# breakout_pmg001.net
KiCad netlist of a schematic drawn in EAGLE
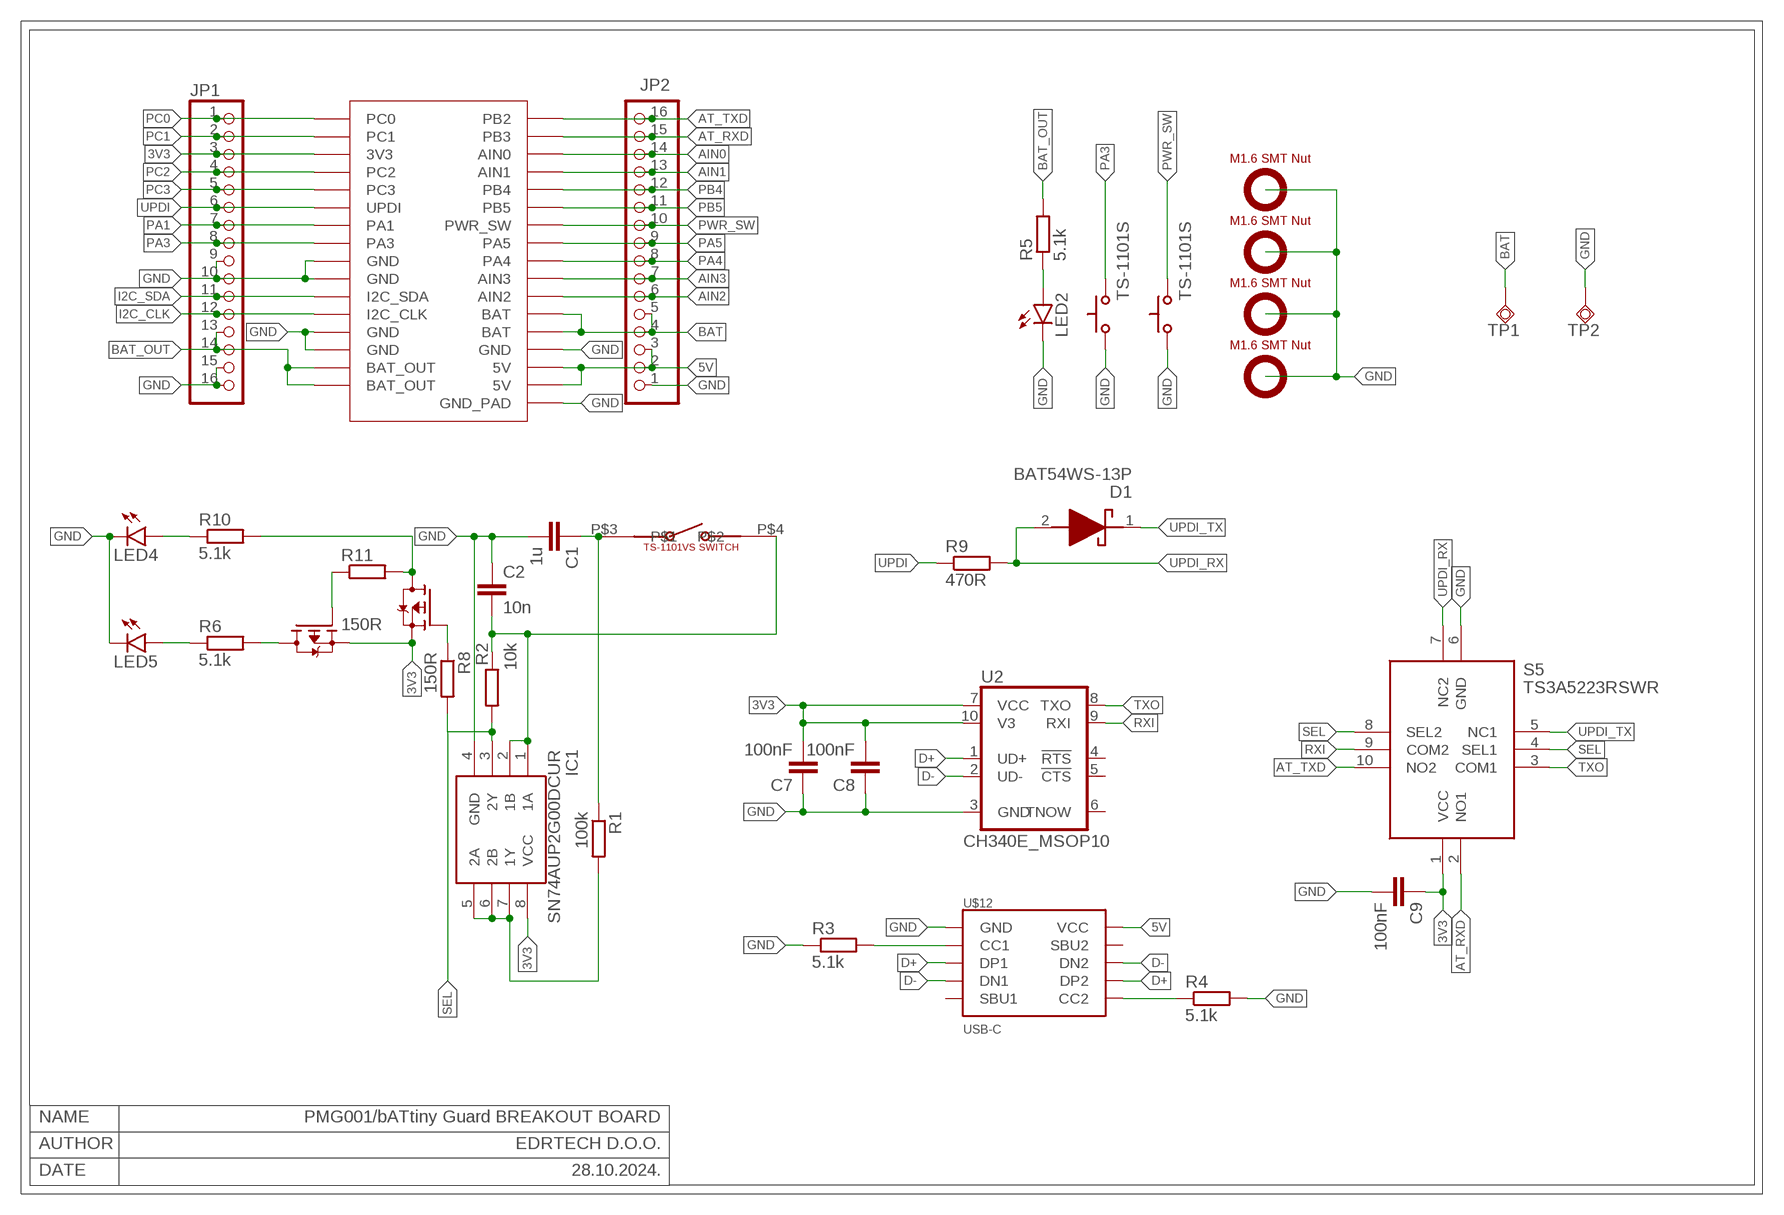
[diagram p0: schematic, sheet 1]

(export (version "E")
  (design (tool "Eeschema 10.0.6"))
  (components
    (comp (ref "C1")
      (value "1u")
      (footprint "eagle-import:C0402")
      (libsource (lib "eagle-import") (part "C-EUC0402"))
    )
    (comp (ref "C2")
      (value "10n")
      (footprint "eagle-import:C0402")
      (libsource (lib "eagle-import") (part "C-EUC0402"))
    )
    (comp (ref "C7")
      (value "100nF")
      (footprint "eagle-import:C0402")
      (libsource (lib "eagle-import") (part "C-EUC0402"))
    )
    (comp (ref "C8")
      (value "100nF")
      (footprint "eagle-import:C0402")
      (libsource (lib "eagle-import") (part "C-EUC0402"))
    )
    (comp (ref "C9")
      (value "100nF")
      (footprint "eagle-import:C0402")
      (libsource (lib "eagle-import") (part "C-EUC0402"))
    )
    (comp (ref "D1")
      (value "BAT54WS-13P")
      (footprint "eagle-import:SOD2512X115N")
      (libsource (lib "eagle-import") (part "BAT54WS-13P"))
    )
    (comp (ref "IC1")
      (value "SN74AUP2G00DCUR")
      (footprint "eagle-import:SOP50P310X90-8N")
      (fields (field (name "MOUSER_PART_NUMBER") "595-SN74AUP2G00DCUR"))
      (libsource (lib "eagle-import") (part "SN74AUP2G00DCUR"))
    )
    (comp (ref "JP1")
      (value "PINHD-1X16")
      (footprint "eagle-import:1X16")
      (libsource (lib "eagle-import") (part "PINHD-1X16"))
    )
    (comp (ref "JP2")
      (value "PINHD-1X16")
      (footprint "eagle-import:1X16")
      (libsource (lib "eagle-import") (part "PINHD-1X16"))
    )
    (comp (ref "LED2")
      (value "LEDCHIP-LED0603")
      (footprint "eagle-import:CHIP-LED0603")
      (libsource (lib "eagle-import") (part "LEDCHIP-LED0603"))
    )
    (comp (ref "LED4")
      (value "LEDCHIP-LED0603")
      (footprint "eagle-import:CHIP-LED0603")
      (libsource (lib "eagle-import") (part "LEDCHIP-LED0603"))
    )
    (comp (ref "LED5")
      (value "LEDCHIP-LED0603")
      (footprint "eagle-import:CHIP-LED0603")
      (libsource (lib "eagle-import") (part "LEDCHIP-LED0603"))
    )
    (comp (ref "Q1")
      (value "NTK3139PT1G")
      (footprint "eagle-import:SOTFL40P120X55-3N")
      (fields (field (name "MOUSER_PART_NUMBER") "863-NTK3139PT1G"))
      (libsource (lib "eagle-import") (part "NTK3139PT1G"))
    )
    (comp (ref "Q2")
      (value "NTK3139PT1G")
      (footprint "eagle-import:SOTFL40P120X55-3N")
      (fields (field (name "MOUSER_PART_NUMBER") "863-NTK3139PT1G"))
      (libsource (lib "eagle-import") (part "NTK3139PT1G"))
    )
    (comp (ref "R1")
      (value "100k")
      (footprint "eagle-import:R0402")
      (libsource (lib "eagle-import") (part "R-EU_R0402"))
    )
    (comp (ref "R2")
      (value "10k")
      (footprint "eagle-import:R0402")
      (libsource (lib "eagle-import") (part "R-EU_R0402"))
    )
    (comp (ref "R3")
      (value "5.1k")
      (footprint "eagle-import:R0402")
      (libsource (lib "eagle-import") (part "R-EU_R0402"))
    )
    (comp (ref "R4")
      (value "5.1k")
      (footprint "eagle-import:R0402")
      (libsource (lib "eagle-import") (part "R-EU_R0402"))
    )
    (comp (ref "R5")
      (value "5.1k")
      (footprint "eagle-import:R0402")
      (libsource (lib "eagle-import") (part "R-EU_R0402"))
    )
    (comp (ref "R6")
      (value "5.1k")
      (footprint "eagle-import:R0402")
      (libsource (lib "eagle-import") (part "R-EU_R0402"))
    )
    (comp (ref "R8")
      (value "150R")
      (footprint "eagle-import:R0402")
      (libsource (lib "eagle-import") (part "R-EU_R0402"))
    )
    (comp (ref "R9")
      (value "470R")
      (footprint "eagle-import:R0402")
      (libsource (lib "eagle-import") (part "R-EU_R0402"))
    )
    (comp (ref "R10")
      (value "5.1k")
      (footprint "eagle-import:R0402")
      (libsource (lib "eagle-import") (part "R-EU_R0402"))
    )
    (comp (ref "R11")
      (value "150R")
      (footprint "eagle-import:R0402")
      (libsource (lib "eagle-import") (part "R-EU_R0402"))
    )
    (comp (ref "S5")
      (value "TS3A5223RSWR")
      (footprint "eagle-import:RSW(RPUQFNN10)")
      (fields (field (name "MOUSER_PART_NUMBER") "595-TS3A5223RSWR"))
      (libsource (lib "eagle-import") (part "TS3A5223RSWR"))
    )
    (comp (ref "TP1")
      (value "TPSQTP19SQ")
      (footprint "eagle-import:TP19SQ")
      (libsource (lib "eagle-import") (part "TPSQTP19SQ"))
    )
    (comp (ref "TP2")
      (value "TPSQTP19SQ")
      (footprint "eagle-import:TP19SQ")
      (libsource (lib "eagle-import") (part "TPSQTP19SQ"))
    )
    (comp (ref "U$1")
      (value "TS-1101S")
      (footprint "eagle-import:TS-1101S")
      (libsource (lib "eagle-import") (part "TS-1101S"))
    )
    (comp (ref "U$2")
      (value "TS-1101VS-C-A-A")
      (footprint "eagle-import:TS-1101VS-C-A-A")
      (libsource (lib "eagle-import") (part "TS-1101VS-C-A-A"))
    )
    (comp (ref "U$4")
      (value "TS-1101S")
      (footprint "eagle-import:TS-1101S")
      (libsource (lib "eagle-import") (part "TS-1101S"))
    )
    (comp (ref "U$7")
      (value "PMG001")
      (footprint "eagle-import:PMG001")
      (libsource (lib "eagle-import") (part "PMG001"))
    )
    (comp (ref "U$8")
      (value "SMTSO16")
      (footprint "eagle-import:SMTSO16")
      (libsource (lib "eagle-import") (part "SMTSO16"))
    )
    (comp (ref "U$9")
      (value "SMTSO16")
      (footprint "eagle-import:SMTSO16")
      (libsource (lib "eagle-import") (part "SMTSO16"))
    )
    (comp (ref "U$10")
      (value "SMTSO16")
      (footprint "eagle-import:SMTSO16")
      (libsource (lib "eagle-import") (part "SMTSO16"))
    )
    (comp (ref "U$11")
      (value "SMTSO16")
      (footprint "eagle-import:SMTSO16")
      (libsource (lib "eagle-import") (part "SMTSO16"))
    )
    (comp (ref "U$12")
      (value "USB-C")
      (footprint "eagle-import:USB-C")
      (libsource (lib "eagle-import") (part "USB-C"))
    )
    (comp (ref "U2")
      (value "CH340E_MSOP10")
      (footprint "eagle-import:MSOP10")
      (fields (field (name "MF") "WCH") (field (name "MP") "CH340E"))
      (libsource (lib "eagle-import") (part "CH340E_MSOP10"))
    )
  )
  (nets
    (net (code "1") (name "3V3") (class "Default")
      (node (ref "C7") (pin "2") (pinfunction "2_2") (pintype "passive"))
      (node (ref "C8") (pin "2") (pinfunction "2_2") (pintype "passive"))
      (node (ref "C9") (pin "1") (pinfunction "1_1") (pintype "passive"))
      (node (ref "IC1") (pin "8") (pinfunction "VCC_8") (pintype "bidirectional"))
      (node (ref "JP1") (pin "3") (pinfunction "3_3") (pintype "passive"))
      (node (ref "Q1") (pin "2") (pinfunction "S_2") (pintype "passive"))
      (node (ref "Q2") (pin "2") (pinfunction "S_2") (pintype "passive"))
      (node (ref "S5") (pin "1") (pinfunction "VCC_1") (pintype "power_in"))
      (node (ref "U$7") (pin "P$3") (pinfunction "3V3_P$3") (pintype "bidirectional"))
      (node (ref "U2") (pin "10") (pinfunction "V3_10") (pintype "bidirectional"))
      (node (ref "U2") (pin "7") (pinfunction "VCC_7") (pintype "bidirectional"))
    )
    (net (code "2") (name "5V") (class "Default")
      (node (ref "JP2") (pin "2") (pinfunction "2_2") (pintype "passive"))
      (node (ref "JP2") (pin "3") (pinfunction "3_3") (pintype "passive"))
      (node (ref "U$12") (pin "VCC@1") (pinfunction "VCC_VCC@1") (pintype "bidirectional"))
      (node (ref "U$12") (pin "VCC@2") (pinfunction "VCC_VCC@2") (pintype "bidirectional"))
      (node (ref "U$7") (pin "P$17") (pinfunction "5V_P$17") (pintype "bidirectional"))
      (node (ref "U$7") (pin "P$18") (pinfunction "5V_P$18") (pintype "bidirectional"))
    )
    (net (code "3") (name "AIN0") (class "Default")
      (node (ref "JP2") (pin "14") (pinfunction "14_14") (pintype "passive"))
      (node (ref "U$7") (pin "P$30") (pinfunction "AIN0_P$30") (pintype "bidirectional"))
    )
    (net (code "4") (name "AIN1") (class "Default")
      (node (ref "JP2") (pin "13") (pinfunction "13_13") (pintype "passive"))
      (node (ref "U$7") (pin "P$29") (pinfunction "AIN1_P$29") (pintype "bidirectional"))
    )
    (net (code "5") (name "AIN2") (class "Default")
      (node (ref "JP2") (pin "6") (pinfunction "6_6") (pintype "passive"))
      (node (ref "U$7") (pin "P$22") (pinfunction "AIN2_P$22") (pintype "bidirectional"))
    )
    (net (code "6") (name "AIN3") (class "Default")
      (node (ref "JP2") (pin "7") (pinfunction "7_7") (pintype "passive"))
      (node (ref "U$7") (pin "P$23") (pinfunction "AIN3_P$23") (pintype "bidirectional"))
    )
    (net (code "7") (name "AT_RXD") (class "Default")
      (node (ref "JP2") (pin "15") (pinfunction "15_15") (pintype "passive"))
      (node (ref "S5") (pin "2") (pinfunction "NO1_2") (pintype "bidirectional"))
      (node (ref "U$7") (pin "P$31") (pinfunction "PB3_P$31") (pintype "bidirectional"))
    )
    (net (code "8") (name "AT_TXD") (class "Default")
      (node (ref "JP2") (pin "16") (pinfunction "16_16") (pintype "passive"))
      (node (ref "S5") (pin "10") (pinfunction "NO2_10") (pintype "bidirectional"))
      (node (ref "U$7") (pin "P$32") (pinfunction "PB2_P$32") (pintype "bidirectional"))
    )
    (net (code "9") (name "BAT") (class "Default")
      (node (ref "JP2") (pin "4") (pinfunction "4_4") (pintype "passive"))
      (node (ref "JP2") (pin "5") (pinfunction "5_5") (pintype "passive"))
      (node (ref "TP1") (pin "TP") (pinfunction "TP_TP") (pintype "input"))
      (node (ref "U$7") (pin "P$20") (pinfunction "BAT_P$20") (pintype "bidirectional"))
      (node (ref "U$7") (pin "P$21") (pinfunction "BAT_P$21") (pintype "bidirectional"))
    )
    (net (code "10") (name "BAT_OUT") (class "Default")
      (node (ref "JP1") (pin "13") (pinfunction "13_13") (pintype "passive"))
      (node (ref "JP1") (pin "14") (pinfunction "14_14") (pintype "passive"))
      (node (ref "R5") (pin "2") (pinfunction "2_2") (pintype "passive"))
      (node (ref "U$7") (pin "P$15") (pinfunction "BAT_OUT_P$15") (pintype "bidirectional"))
      (node (ref "U$7") (pin "P$16") (pinfunction "BAT_OUT_P$16") (pintype "bidirectional"))
    )
    (net (code "11") (name "D+") (class "Default")
      (node (ref "U$12") (pin "DP1") (pinfunction "DP1_DP1") (pintype "bidirectional"))
      (node (ref "U$12") (pin "DP2") (pinfunction "DP2_DP2") (pintype "bidirectional"))
      (node (ref "U2") (pin "1") (pinfunction "UD+_1") (pintype "bidirectional"))
    )
    (net (code "12") (name "D-") (class "Default")
      (node (ref "U$12") (pin "DN1") (pinfunction "DN1_DN1") (pintype "bidirectional"))
      (node (ref "U$12") (pin "DN2") (pinfunction "DN2_DN2") (pintype "bidirectional"))
      (node (ref "U2") (pin "2") (pinfunction "UD-_2") (pintype "bidirectional"))
    )
    (net (code "13") (name "GND") (class "Default")
      (node (ref "C1") (pin "2") (pinfunction "2_2") (pintype "passive"))
      (node (ref "C2") (pin "1") (pinfunction "1_1") (pintype "passive"))
      (node (ref "C7") (pin "1") (pinfunction "1_1") (pintype "passive"))
      (node (ref "C8") (pin "1") (pinfunction "1_1") (pintype "passive"))
      (node (ref "C9") (pin "2") (pinfunction "2_2") (pintype "passive"))
      (node (ref "IC1") (pin "4") (pinfunction "GND_4") (pintype "bidirectional"))
      (node (ref "JP1") (pin "10") (pinfunction "10_10") (pintype "passive"))
      (node (ref "JP1") (pin "15") (pinfunction "15_15") (pintype "passive"))
      (node (ref "JP1") (pin "16") (pinfunction "16_16") (pintype "passive"))
      (node (ref "JP1") (pin "9") (pinfunction "9_9") (pintype "passive"))
      (node (ref "JP2") (pin "1") (pinfunction "1_1") (pintype "passive"))
      (node (ref "LED2") (pin "C") (pinfunction "C_C") (pintype "passive"))
      (node (ref "LED4") (pin "C") (pinfunction "C_C") (pintype "passive"))
      (node (ref "LED5") (pin "C") (pinfunction "C_C") (pintype "passive"))
      (node (ref "R3") (pin "1") (pinfunction "1_1") (pintype "passive"))
      (node (ref "R4") (pin "2") (pinfunction "2_2") (pintype "passive"))
      (node (ref "S5") (pin "6") (pinfunction "GND_6") (pintype "power_in"))
      (node (ref "TP2") (pin "TP") (pinfunction "TP_TP") (pintype "input"))
      (node (ref "U$1") (pin "P$1") (pinfunction "1_P$1") (pintype "bidirectional"))
      (node (ref "U$10") (pin "P$1") (pinfunction "P$1_P$1") (pintype "bidirectional"))
      (node (ref "U$11") (pin "P$1") (pinfunction "P$1_P$1") (pintype "bidirectional"))
      (node (ref "U$12") (pin "GND@1") (pinfunction "GND_GND@1") (pintype "bidirectional"))
      (node (ref "U$12") (pin "GND@2") (pinfunction "GND_GND@2") (pintype "bidirectional"))
      (node (ref "U$12") (pin "P$1") (pinfunction "GND_P$1") (pintype "bidirectional"))
      (node (ref "U$12") (pin "P$2") (pinfunction "GND_P$2") (pintype "bidirectional"))
      (node (ref "U$12") (pin "P$3") (pinfunction "GND_P$3") (pintype "bidirectional"))
      (node (ref "U$12") (pin "P$4") (pinfunction "GND_P$4") (pintype "bidirectional"))
      (node (ref "U$4") (pin "P$1") (pinfunction "1_P$1") (pintype "bidirectional"))
      (node (ref "U$7") (pin "P$10") (pinfunction "GND_P$10") (pintype "bidirectional"))
      (node (ref "U$7") (pin "P$13") (pinfunction "GND_P$13") (pintype "bidirectional"))
      (node (ref "U$7") (pin "P$14") (pinfunction "GND_P$14") (pintype "bidirectional"))
      (node (ref "U$7") (pin "P$19") (pinfunction "GND_P$19") (pintype "bidirectional"))
      (node (ref "U$7") (pin "P$33") (pinfunction "GND_PAD_P$33") (pintype "bidirectional"))
      (node (ref "U$7") (pin "P$9") (pinfunction "GND_P$9") (pintype "bidirectional"))
      (node (ref "U$8") (pin "P$1") (pinfunction "P$1_P$1") (pintype "bidirectional"))
      (node (ref "U$9") (pin "P$1") (pinfunction "P$1_P$1") (pintype "bidirectional"))
      (node (ref "U2") (pin "3") (pinfunction "GND_3") (pintype "bidirectional"))
    )
    (net (code "14") (name "I2C_CLK") (class "Default")
      (node (ref "JP1") (pin "12") (pinfunction "12_12") (pintype "passive"))
      (node (ref "U$7") (pin "P$12") (pinfunction "I2C_CLK_P$12") (pintype "bidirectional"))
    )
    (net (code "15") (name "I2C_SDA") (class "Default")
      (node (ref "JP1") (pin "11") (pinfunction "11_11") (pintype "passive"))
      (node (ref "U$7") (pin "P$11") (pinfunction "I2C_SDA_P$11") (pintype "bidirectional"))
    )
    (net (code "16") (name "Net-(IC1-1A)") (class "Default")
      (node (ref "C2") (pin "2") (pinfunction "2_2") (pintype "passive"))
      (node (ref "IC1") (pin "1") (pinfunction "1A_1") (pintype "bidirectional"))
      (node (ref "IC1") (pin "2") (pinfunction "1B_2") (pintype "bidirectional"))
      (node (ref "R2") (pin "1") (pinfunction "1_1") (pintype "passive"))
      (node (ref "U$2") (pin "P$4") (pinfunction "P$2_P$4") (pintype "bidirectional"))
    )
    (net (code "17") (name "Net-(IC1-1Y)") (class "Default")
      (node (ref "IC1") (pin "5") (pinfunction "2A_5") (pintype "bidirectional"))
      (node (ref "IC1") (pin "6") (pinfunction "2B_6") (pintype "bidirectional"))
      (node (ref "IC1") (pin "7") (pinfunction "1Y_7") (pintype "bidirectional"))
      (node (ref "R1") (pin "2") (pinfunction "2_2") (pintype "passive"))
    )
    (net (code "18") (name "Net-(LED2-PadA)") (class "Default")
      (node (ref "LED2") (pin "A") (pinfunction "A_A") (pintype "passive"))
      (node (ref "R5") (pin "1") (pinfunction "1_1") (pintype "passive"))
    )
    (net (code "19") (name "Net-(LED4-PadA)") (class "Default")
      (node (ref "LED4") (pin "A") (pinfunction "A_A") (pintype "passive"))
      (node (ref "R10") (pin "1") (pinfunction "1_1") (pintype "passive"))
    )
    (net (code "20") (name "Net-(LED5-PadA)") (class "Default")
      (node (ref "LED5") (pin "A") (pinfunction "A_A") (pintype "passive"))
      (node (ref "R6") (pin "1") (pinfunction "1_1") (pintype "passive"))
    )
    (net (code "21") (name "Net-(Q1-D)") (class "Default")
      (node (ref "Q1") (pin "3") (pinfunction "D_3") (pintype "passive"))
      (node (ref "R10") (pin "2") (pinfunction "2_2") (pintype "passive"))
      (node (ref "R11") (pin "2") (pinfunction "2_2") (pintype "passive"))
    )
    (net (code "22") (name "Net-(Q1-G)") (class "Default")
      (node (ref "Q1") (pin "1") (pinfunction "G_1") (pintype "passive"))
      (node (ref "R8") (pin "1") (pinfunction "1_1") (pintype "passive"))
    )
    (net (code "23") (name "Net-(Q2-D)") (class "Default")
      (node (ref "Q2") (pin "3") (pinfunction "D_3") (pintype "passive"))
      (node (ref "R6") (pin "2") (pinfunction "2_2") (pintype "passive"))
    )
    (net (code "24") (name "Net-(Q2-G)") (class "Default")
      (node (ref "Q2") (pin "1") (pinfunction "G_1") (pintype "passive"))
      (node (ref "R11") (pin "1") (pinfunction "1_1") (pintype "passive"))
    )
    (net (code "25") (name "Net-(R3-Pad2)") (class "Default")
      (node (ref "R3") (pin "2") (pinfunction "2_2") (pintype "passive"))
      (node (ref "U$12") (pin "CC1") (pinfunction "CC1_CC1") (pintype "bidirectional"))
    )
    (net (code "26") (name "Net-(R4-Pad1)") (class "Default")
      (node (ref "R4") (pin "1") (pinfunction "1_1") (pintype "passive"))
      (node (ref "U$12") (pin "CC2") (pinfunction "CC2_CC2") (pintype "bidirectional"))
    )
    (net (code "27") (name "Net-(U$2-P$1)") (class "Default")
      (node (ref "C1") (pin "1") (pinfunction "1_1") (pintype "passive"))
      (node (ref "R1") (pin "1") (pinfunction "1_1") (pintype "passive"))
      (node (ref "U$2") (pin "P$3") (pinfunction "P$1_P$3") (pintype "bidirectional"))
    )
    (net (code "28") (name "PA1") (class "Default")
      (node (ref "JP1") (pin "7") (pinfunction "7_7") (pintype "passive"))
      (node (ref "U$7") (pin "P$7") (pinfunction "PA1_P$7") (pintype "bidirectional"))
    )
    (net (code "29") (name "PA3") (class "Default")
      (node (ref "JP1") (pin "8") (pinfunction "8_8") (pintype "passive"))
      (node (ref "U$1") (pin "P$2") (pinfunction "2_P$2") (pintype "bidirectional"))
      (node (ref "U$7") (pin "P$8") (pinfunction "PA3_P$8") (pintype "bidirectional"))
    )
    (net (code "30") (name "PA4") (class "Default")
      (node (ref "JP2") (pin "8") (pinfunction "8_8") (pintype "passive"))
      (node (ref "U$7") (pin "P$24") (pinfunction "PA4_P$24") (pintype "bidirectional"))
    )
    (net (code "31") (name "PA5") (class "Default")
      (node (ref "JP2") (pin "9") (pinfunction "9_9") (pintype "passive"))
      (node (ref "U$7") (pin "P$25") (pinfunction "PA5_P$25") (pintype "bidirectional"))
    )
    (net (code "32") (name "PB4") (class "Default")
      (node (ref "JP2") (pin "12") (pinfunction "12_12") (pintype "passive"))
      (node (ref "U$7") (pin "P$28") (pinfunction "PB4_P$28") (pintype "bidirectional"))
    )
    (net (code "33") (name "PB5") (class "Default")
      (node (ref "JP2") (pin "11") (pinfunction "11_11") (pintype "passive"))
      (node (ref "U$7") (pin "P$27") (pinfunction "PB5_P$27") (pintype "bidirectional"))
    )
    (net (code "34") (name "PC0") (class "Default")
      (node (ref "JP1") (pin "1") (pinfunction "1_1") (pintype "passive"))
      (node (ref "U$7") (pin "P$1") (pinfunction "PC0_P$1") (pintype "bidirectional"))
    )
    (net (code "35") (name "PC1") (class "Default")
      (node (ref "JP1") (pin "2") (pinfunction "2_2") (pintype "passive"))
      (node (ref "U$7") (pin "P$2") (pinfunction "PC1_P$2") (pintype "bidirectional"))
    )
    (net (code "36") (name "PC2") (class "Default")
      (node (ref "JP1") (pin "4") (pinfunction "4_4") (pintype "passive"))
      (node (ref "U$7") (pin "P$4") (pinfunction "PC2_P$4") (pintype "bidirectional"))
    )
    (net (code "37") (name "PC3") (class "Default")
      (node (ref "JP1") (pin "5") (pinfunction "5_5") (pintype "passive"))
      (node (ref "U$7") (pin "P$5") (pinfunction "PC3_P$5") (pintype "bidirectional"))
    )
    (net (code "38") (name "PWR_SW") (class "Default")
      (node (ref "JP2") (pin "10") (pinfunction "10_10") (pintype "passive"))
      (node (ref "U$4") (pin "P$2") (pinfunction "2_P$2") (pintype "bidirectional"))
      (node (ref "U$7") (pin "P$26") (pinfunction "PWR_SW_P$26") (pintype "bidirectional"))
    )
    (net (code "39") (name "RXI") (class "Default")
      (node (ref "S5") (pin "9") (pinfunction "COM2_9") (pintype "bidirectional"))
      (node (ref "U2") (pin "9") (pinfunction "RXI_9") (pintype "bidirectional"))
    )
    (net (code "40") (name "SEL") (class "Default")
      (node (ref "IC1") (pin "3") (pinfunction "2Y_3") (pintype "bidirectional"))
      (node (ref "R2") (pin "2") (pinfunction "2_2") (pintype "passive"))
      (node (ref "R8") (pin "2") (pinfunction "2_2") (pintype "passive"))
      (node (ref "S5") (pin "4") (pinfunction "SEL1_4") (pintype "bidirectional"))
      (node (ref "S5") (pin "8") (pinfunction "SEL2_8") (pintype "bidirectional"))
    )
    (net (code "41") (name "TXO") (class "Default")
      (node (ref "S5") (pin "3") (pinfunction "COM1_3") (pintype "bidirectional"))
      (node (ref "U2") (pin "8") (pinfunction "TXO_8") (pintype "bidirectional"))
    )
    (net (code "42") (name "UPDI") (class "Default")
      (node (ref "JP1") (pin "6") (pinfunction "6_6") (pintype "passive"))
      (node (ref "R9") (pin "1") (pinfunction "1_1") (pintype "passive"))
      (node (ref "U$7") (pin "P$6") (pinfunction "UPDI_P$6") (pintype "bidirectional"))
    )
    (net (code "43") (name "UPDI_RX") (class "Default")
      (node (ref "D1") (pin "2") (pinfunction "A_2") (pintype "bidirectional"))
      (node (ref "R9") (pin "2") (pinfunction "2_2") (pintype "passive"))
      (node (ref "S5") (pin "7") (pinfunction "NC2_7") (pintype "bidirectional"))
    )
    (net (code "44") (name "UPDI_TX") (class "Default")
      (node (ref "D1") (pin "1") (pinfunction "K_1") (pintype "bidirectional"))
      (node (ref "S5") (pin "5") (pinfunction "NC1_5") (pintype "bidirectional"))
    )
    (net (code "45") (name "unconnected-(U$12-PadSBU1)") (class "Default")
      (node (ref "U$12") (pin "SBU1") (pinfunction "SBU1_SBU1") (pintype "bidirectional"))
    )
    (net (code "46") (name "unconnected-(U$12-PadSBU2)") (class "Default")
      (node (ref "U$12") (pin "SBU2") (pinfunction "SBU2_SBU2") (pintype "bidirectional"))
    )
    (net (code "47") (name "unconnected-(U2-TNOW-Pad6)") (class "Default")
      (node (ref "U2") (pin "6") (pinfunction "TNOW_6") (pintype "bidirectional"))
    )
    (net (code "48") (name "unconnected-(U2-~{CTS}-Pad5)") (class "Default")
      (node (ref "U2") (pin "5") (pinfunction "~{CTS}_5") (pintype "bidirectional"))
    )
    (net (code "49") (name "unconnected-(U2-~{RTS}-Pad4)") (class "Default")
      (node (ref "U2") (pin "4") (pinfunction "~{RTS}_4") (pintype "bidirectional"))
    )
  )
)
